# eprom_prog.net
KiCad netlist of a schematic drawn in EAGLE
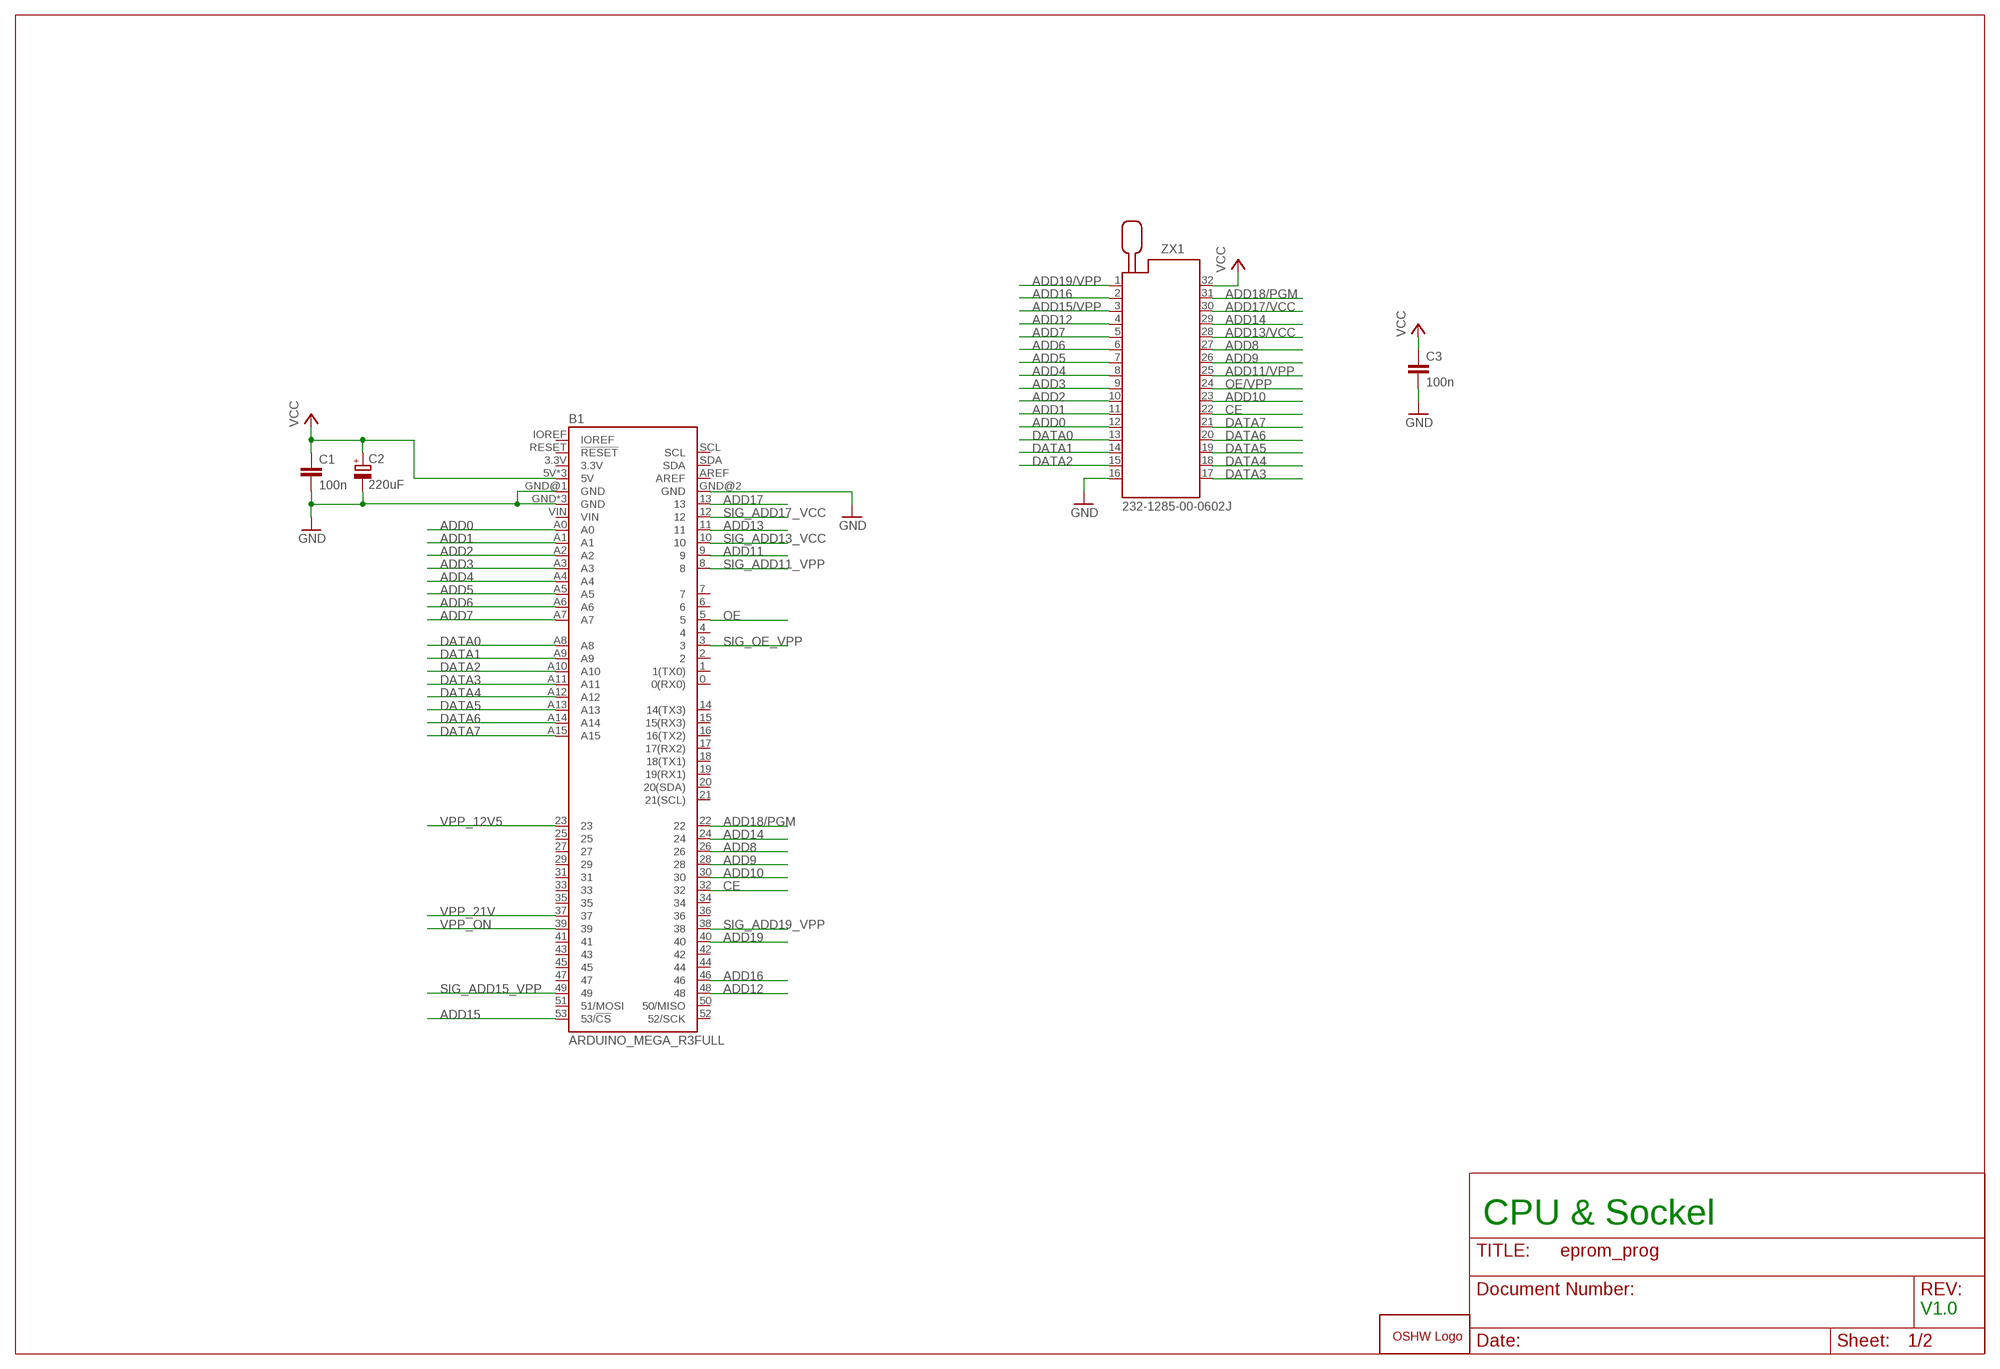
[diagram p0: schematic, sheet 1]
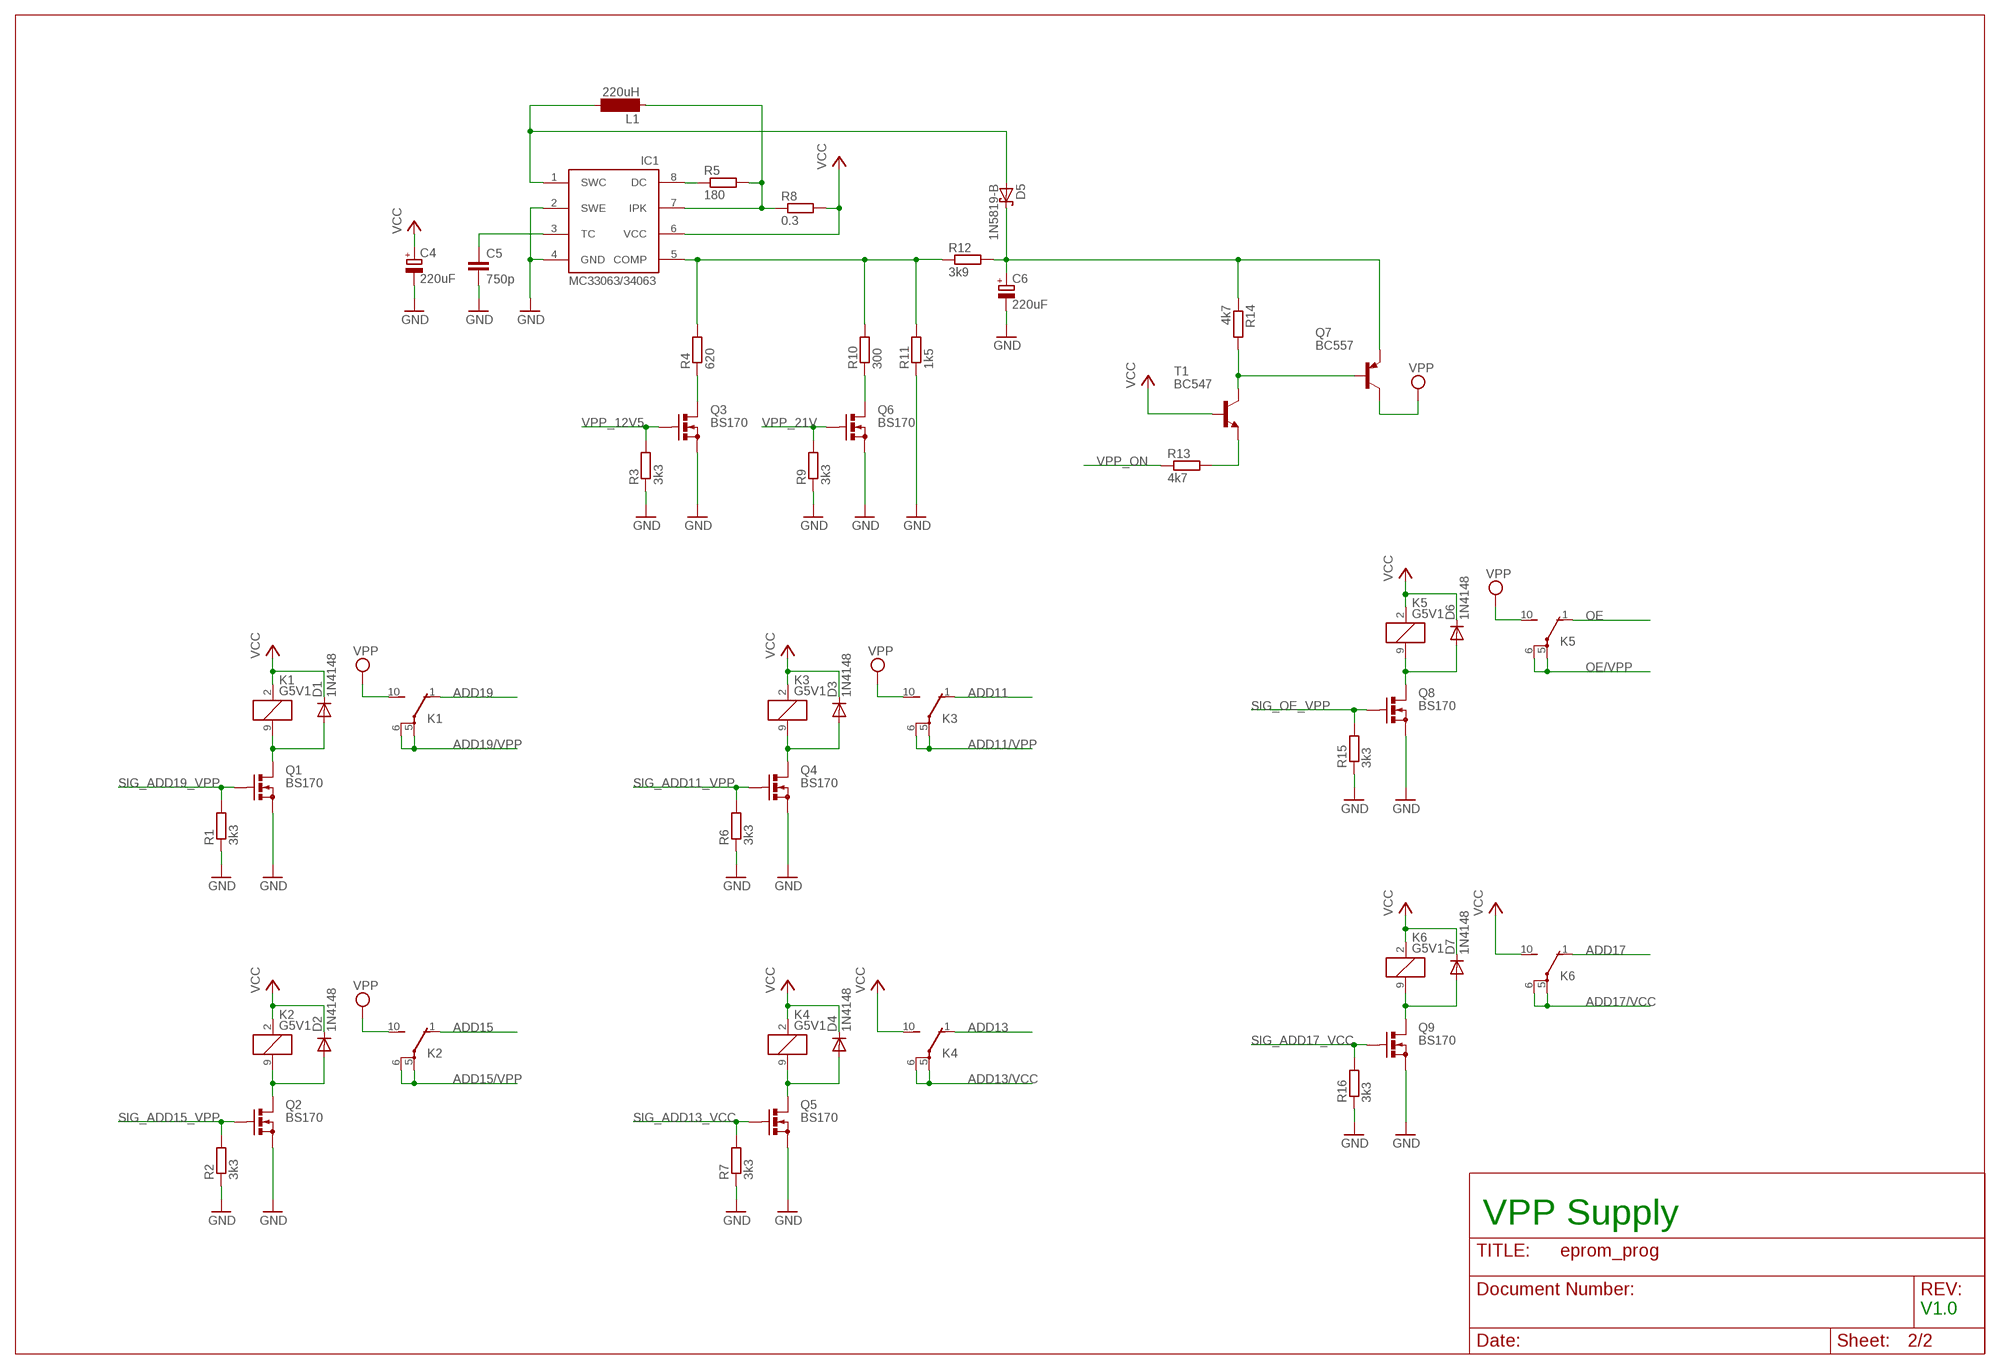
[diagram p1: schematic, sheet 2]

(export (version "E")
  (design (tool "Eeschema 10.0.6"))
  (components
    (comp (ref "B1")
      (value "ARDUINO_MEGA_R3FULL")
      (footprint "eagle-import:ARDUINO_MEGA_NO_SILK")
      (libsource (lib "eagle-import") (part "ARDUINO_MEGA_R3FULL"))
    )
    (comp (ref "C1")
      (value "100n")
      (footprint "eagle-import:C050-024X044")
      (libsource (lib "eagle-import") (part "C-EU050-024X044"))
    )
    (comp (ref "C2")
      (value "220uF")
      (footprint "eagle-import:E2,5-6")
      (libsource (lib "eagle-import") (part "CPOL-EUE2.5-6"))
    )
    (comp (ref "C3")
      (value "100n")
      (footprint "eagle-import:C050-024X044")
      (libsource (lib "eagle-import") (part "C-EU050-024X044"))
    )
    (comp (ref "GOLD_ORB_SM1")
      (value "OSHWLOGOLOGO8MM")
      (footprint "eagle-import:OSHW_8MM")
      (libsource (lib "eagle-import") (part "OSHWLOGOLOGO8MM"))
    )
    (comp (ref "ZX1")
      (value "232-1285-00-0602J")
      (footprint "eagle-import:232-1285-00-0602J")
      (fields (field (name "MF") "3M"))
      (libsource (lib "eagle-import") (part "232-?1285-00-0602J"))
    )
    (comp (ref "C4")
      (value "220uF")
      (footprint "eagle-import:E2,5-6")
      (libsource (lib "eagle-import") (part "CPOL-EUE2.5-6"))
    )
    (comp (ref "C5")
      (value "750p")
      (footprint "eagle-import:C050-024X044")
      (libsource (lib "eagle-import") (part "C-EU050-024X044"))
    )
    (comp (ref "C6")
      (value "220uF")
      (footprint "eagle-import:E2,5-6")
      (libsource (lib "eagle-import") (part "CPOL-EUE2.5-6"))
    )
    (comp (ref "D1")
      (value "1N4148")
      (footprint "eagle-import:DO35-7")
      (libsource (lib "eagle-import") (part "1N4148DO35-7"))
    )
    (comp (ref "D2")
      (value "1N4148")
      (footprint "eagle-import:DO35-7")
      (libsource (lib "eagle-import") (part "1N4148DO35-7"))
    )
    (comp (ref "D3")
      (value "1N4148")
      (footprint "eagle-import:DO35-7")
      (libsource (lib "eagle-import") (part "1N4148DO35-7"))
    )
    (comp (ref "D4")
      (value "1N4148")
      (footprint "eagle-import:DO35-7")
      (libsource (lib "eagle-import") (part "1N4148DO35-7"))
    )
    (comp (ref "D5")
      (value "1N5819-B")
      (footprint "eagle-import:DO41-7.6")
      (libsource (lib "eagle-import") (part "1N5819-B"))
    )
    (comp (ref "D6")
      (value "1N4148")
      (footprint "eagle-import:DO35-7")
      (libsource (lib "eagle-import") (part "1N4148DO35-7"))
    )
    (comp (ref "D7")
      (value "1N4148")
      (footprint "eagle-import:DO35-7")
      (libsource (lib "eagle-import") (part "1N4148DO35-7"))
    )
    (comp (ref "IC1")
      (value "MC33063/MC34063P")
      (footprint "eagle-import:DIL08")
      (libsource (lib "eagle-import") (part "MC33063/MC34063P"))
    )
    (comp (ref "K1")
      (value "G5V1")
      (footprint "eagle-import:G5V1")
      (fields (field (name "MPN") "G5V-1-DC24"))
      (libsource (lib "eagle-import") (part "G5V1"))
    )
    (comp (ref "K2")
      (value "G5V1")
      (footprint "eagle-import:G5V1")
      (fields (field (name "MPN") "G5V-1-DC24"))
      (libsource (lib "eagle-import") (part "G5V1"))
    )
    (comp (ref "K3")
      (value "G5V1")
      (footprint "eagle-import:G5V1")
      (fields (field (name "MPN") "G5V-1-DC24"))
      (libsource (lib "eagle-import") (part "G5V1"))
    )
    (comp (ref "K4")
      (value "G5V1")
      (footprint "eagle-import:G5V1")
      (fields (field (name "MPN") "G5V-1-DC24"))
      (libsource (lib "eagle-import") (part "G5V1"))
    )
    (comp (ref "K5")
      (value "G5V1")
      (footprint "eagle-import:G5V1")
      (fields (field (name "MPN") "G5V-1-DC24"))
      (libsource (lib "eagle-import") (part "G5V1"))
    )
    (comp (ref "K6")
      (value "G5V1")
      (footprint "eagle-import:G5V1")
      (fields (field (name "MPN") "G5V-1-DC24"))
      (libsource (lib "eagle-import") (part "G5V1"))
    )
    (comp (ref "L1")
      (value "220uH")
      (footprint "eagle-import:SD12_1000")
      (libsource (lib "eagle-import") (part "SD12-1000"))
    )
    (comp (ref "Q1")
      (value "BS170")
      (footprint "eagle-import:SOT54E")
      (libsource (lib "eagle-import") (part "BS170"))
    )
    (comp (ref "Q2")
      (value "BS170")
      (footprint "eagle-import:SOT54E")
      (libsource (lib "eagle-import") (part "BS170"))
    )
    (comp (ref "Q3")
      (value "BS170")
      (footprint "eagle-import:SOT54E")
      (libsource (lib "eagle-import") (part "BS170"))
    )
    (comp (ref "Q4")
      (value "BS170")
      (footprint "eagle-import:SOT54E")
      (libsource (lib "eagle-import") (part "BS170"))
    )
    (comp (ref "Q5")
      (value "BS170")
      (footprint "eagle-import:SOT54E")
      (libsource (lib "eagle-import") (part "BS170"))
    )
    (comp (ref "Q6")
      (value "BS170")
      (footprint "eagle-import:SOT54E")
      (libsource (lib "eagle-import") (part "BS170"))
    )
    (comp (ref "Q7")
      (value "BC557")
      (footprint "eagle-import:TO92")
      (libsource (lib "eagle-import") (part "BC557"))
    )
    (comp (ref "Q8")
      (value "BS170")
      (footprint "eagle-import:SOT54E")
      (libsource (lib "eagle-import") (part "BS170"))
    )
    (comp (ref "Q9")
      (value "BS170")
      (footprint "eagle-import:SOT54E")
      (libsource (lib "eagle-import") (part "BS170"))
    )
    (comp (ref "R1")
      (value "3k3")
      (footprint "eagle-import:0207_2V")
      (libsource (lib "eagle-import") (part "R-EU_0207/2V"))
    )
    (comp (ref "R2")
      (value "3k3")
      (footprint "eagle-import:0207_2V")
      (libsource (lib "eagle-import") (part "R-EU_0207/2V"))
    )
    (comp (ref "R3")
      (value "3k3")
      (footprint "eagle-import:0207_2V")
      (libsource (lib "eagle-import") (part "R-EU_0207/2V"))
    )
    (comp (ref "R4")
      (value "620")
      (footprint "eagle-import:0207_2V")
      (libsource (lib "eagle-import") (part "R-EU_0207/2V"))
    )
    (comp (ref "R5")
      (value "180")
      (footprint "eagle-import:0207_2V")
      (libsource (lib "eagle-import") (part "R-EU_0207/2V"))
    )
    (comp (ref "R6")
      (value "3k3")
      (footprint "eagle-import:0207_2V")
      (libsource (lib "eagle-import") (part "R-EU_0207/2V"))
    )
    (comp (ref "R7")
      (value "3k3")
      (footprint "eagle-import:0207_2V")
      (libsource (lib "eagle-import") (part "R-EU_0207/2V"))
    )
    (comp (ref "R8")
      (value "0.3")
      (footprint "eagle-import:0207_2V")
      (libsource (lib "eagle-import") (part "R-EU_0207/2V"))
    )
    (comp (ref "R9")
      (value "3k3")
      (footprint "eagle-import:0207_2V")
      (libsource (lib "eagle-import") (part "R-EU_0207/2V"))
    )
    (comp (ref "R10")
      (value "300")
      (footprint "eagle-import:0207_2V")
      (libsource (lib "eagle-import") (part "R-EU_0207/2V"))
    )
    (comp (ref "R11")
      (value "1k5")
      (footprint "eagle-import:0207_2V")
      (libsource (lib "eagle-import") (part "R-EU_0207/2V"))
    )
    (comp (ref "R12")
      (value "3k9")
      (footprint "eagle-import:0207_2V")
      (libsource (lib "eagle-import") (part "R-EU_0207/2V"))
    )
    (comp (ref "R13")
      (value "4k7")
      (footprint "eagle-import:0207_2V")
      (libsource (lib "eagle-import") (part "R-EU_0207/2V"))
    )
    (comp (ref "R14")
      (value "4k7")
      (footprint "eagle-import:0207_2V")
      (libsource (lib "eagle-import") (part "R-EU_0207/2V"))
    )
    (comp (ref "R15")
      (value "3k3")
      (footprint "eagle-import:0207_2V")
      (libsource (lib "eagle-import") (part "R-EU_0207/2V"))
    )
    (comp (ref "R16")
      (value "3k3")
      (footprint "eagle-import:0207_2V")
      (libsource (lib "eagle-import") (part "R-EU_0207/2V"))
    )
    (comp (ref "T1")
      (value "BC547")
      (footprint "eagle-import:TO92")
      (libsource (lib "eagle-import") (part "BC547"))
    )
  )
  (nets
    (net (code "1") (name "ADD0") (class "Default")
      (node (ref "B1") (pin "A0") (pinfunction "A0_A0") (pintype "bidirectional"))
      (node (ref "ZX1") (pin "12") (pinfunction "12_12") (pintype "passive"))
    )
    (net (code "2") (name "ADD1") (class "Default")
      (node (ref "B1") (pin "A1") (pinfunction "A1_A1") (pintype "bidirectional"))
      (node (ref "ZX1") (pin "11") (pinfunction "11_11") (pintype "passive"))
    )
    (net (code "3") (name "ADD2") (class "Default")
      (node (ref "B1") (pin "A2") (pinfunction "A2_A2") (pintype "bidirectional"))
      (node (ref "ZX1") (pin "10") (pinfunction "10_10") (pintype "passive"))
    )
    (net (code "4") (name "ADD3") (class "Default")
      (node (ref "B1") (pin "A3") (pinfunction "A3_A3") (pintype "bidirectional"))
      (node (ref "ZX1") (pin "9") (pinfunction "9_9") (pintype "passive"))
    )
    (net (code "5") (name "ADD4") (class "Default")
      (node (ref "B1") (pin "A4") (pinfunction "A4_A4") (pintype "bidirectional"))
      (node (ref "ZX1") (pin "8") (pinfunction "8_8") (pintype "passive"))
    )
    (net (code "6") (name "ADD5") (class "Default")
      (node (ref "B1") (pin "A5") (pinfunction "A5_A5") (pintype "bidirectional"))
      (node (ref "ZX1") (pin "7") (pinfunction "7_7") (pintype "passive"))
    )
    (net (code "7") (name "ADD6") (class "Default")
      (node (ref "B1") (pin "A6") (pinfunction "A6_A6") (pintype "bidirectional"))
      (node (ref "ZX1") (pin "6") (pinfunction "6_6") (pintype "passive"))
    )
    (net (code "8") (name "ADD7") (class "Default")
      (node (ref "B1") (pin "A7") (pinfunction "A7_A7") (pintype "bidirectional"))
      (node (ref "ZX1") (pin "5") (pinfunction "5_5") (pintype "passive"))
    )
    (net (code "9") (name "ADD8") (class "Default")
      (node (ref "B1") (pin "26") (pinfunction "26_26") (pintype "bidirectional"))
      (node (ref "ZX1") (pin "27") (pinfunction "27_27") (pintype "passive"))
    )
    (net (code "10") (name "ADD9") (class "Default")
      (node (ref "B1") (pin "28") (pinfunction "28_28") (pintype "bidirectional"))
      (node (ref "ZX1") (pin "26") (pinfunction "26_26") (pintype "passive"))
    )
    (net (code "11") (name "ADD10") (class "Default")
      (node (ref "B1") (pin "30") (pinfunction "30_30") (pintype "bidirectional"))
      (node (ref "ZX1") (pin "23") (pinfunction "23_23") (pintype "passive"))
    )
    (net (code "12") (name "ADD11") (class "Default")
      (node (ref "B1") (pin "9") (pinfunction "9_9") (pintype "bidirectional"))
      (node (ref "K3") (pin "1") (pinfunction "O_1") (pintype "passive"))
    )
    (net (code "13") (name "ADD11{slash}VPP") (class "Default")
      (node (ref "K3") (pin "5") (pinfunction "P_5") (pintype "passive"))
      (node (ref "K3") (pin "6") (pinfunction "P_6") (pintype "passive"))
      (node (ref "ZX1") (pin "25") (pinfunction "25_25") (pintype "passive"))
    )
    (net (code "14") (name "ADD12") (class "Default")
      (node (ref "B1") (pin "48") (pinfunction "48_48") (pintype "bidirectional"))
      (node (ref "ZX1") (pin "4") (pinfunction "4_4") (pintype "passive"))
    )
    (net (code "15") (name "ADD13") (class "Default")
      (node (ref "B1") (pin "11") (pinfunction "11_11") (pintype "bidirectional"))
      (node (ref "K4") (pin "1") (pinfunction "O_1") (pintype "passive"))
    )
    (net (code "16") (name "ADD13{slash}VCC") (class "Default")
      (node (ref "K4") (pin "5") (pinfunction "P_5") (pintype "passive"))
      (node (ref "K4") (pin "6") (pinfunction "P_6") (pintype "passive"))
      (node (ref "ZX1") (pin "28") (pinfunction "28_28") (pintype "passive"))
    )
    (net (code "17") (name "ADD14") (class "Default")
      (node (ref "B1") (pin "24") (pinfunction "24_24") (pintype "bidirectional"))
      (node (ref "ZX1") (pin "29") (pinfunction "29_29") (pintype "passive"))
    )
    (net (code "18") (name "ADD15") (class "Default")
      (node (ref "B1") (pin "53") (pinfunction "53/~{CS}_53") (pintype "bidirectional"))
      (node (ref "K2") (pin "1") (pinfunction "O_1") (pintype "passive"))
    )
    (net (code "19") (name "ADD15{slash}VPP") (class "Default")
      (node (ref "K2") (pin "5") (pinfunction "P_5") (pintype "passive"))
      (node (ref "K2") (pin "6") (pinfunction "P_6") (pintype "passive"))
      (node (ref "ZX1") (pin "3") (pinfunction "3_3") (pintype "passive"))
    )
    (net (code "20") (name "ADD16") (class "Default")
      (node (ref "B1") (pin "46") (pinfunction "46_46") (pintype "bidirectional"))
      (node (ref "ZX1") (pin "2") (pinfunction "2_2") (pintype "passive"))
    )
    (net (code "21") (name "ADD17") (class "Default")
      (node (ref "B1") (pin "13") (pinfunction "13_13") (pintype "bidirectional"))
      (node (ref "K6") (pin "1") (pinfunction "O_1") (pintype "passive"))
    )
    (net (code "22") (name "ADD17{slash}VCC") (class "Default")
      (node (ref "K6") (pin "5") (pinfunction "P_5") (pintype "passive"))
      (node (ref "K6") (pin "6") (pinfunction "P_6") (pintype "passive"))
      (node (ref "ZX1") (pin "30") (pinfunction "30_30") (pintype "passive"))
    )
    (net (code "23") (name "ADD18{slash}PGM") (class "Default")
      (node (ref "B1") (pin "22") (pinfunction "22_22") (pintype "bidirectional"))
      (node (ref "ZX1") (pin "31") (pinfunction "31_31") (pintype "passive"))
    )
    (net (code "24") (name "ADD19") (class "Default")
      (node (ref "B1") (pin "40") (pinfunction "40_40") (pintype "bidirectional"))
      (node (ref "K1") (pin "1") (pinfunction "O_1") (pintype "passive"))
    )
    (net (code "25") (name "ADD19{slash}VPP") (class "Default")
      (node (ref "K1") (pin "5") (pinfunction "P_5") (pintype "passive"))
      (node (ref "K1") (pin "6") (pinfunction "P_6") (pintype "passive"))
      (node (ref "ZX1") (pin "1") (pinfunction "1_1") (pintype "passive"))
    )
    (net (code "26") (name "CE") (class "Default")
      (node (ref "B1") (pin "32") (pinfunction "32_32") (pintype "bidirectional"))
      (node (ref "ZX1") (pin "22") (pinfunction "22_22") (pintype "passive"))
    )
    (net (code "27") (name "DATA0") (class "Default")
      (node (ref "B1") (pin "A8") (pinfunction "A8_A8") (pintype "bidirectional"))
      (node (ref "ZX1") (pin "13") (pinfunction "13_13") (pintype "passive"))
    )
    (net (code "28") (name "DATA1") (class "Default")
      (node (ref "B1") (pin "A9") (pinfunction "A9_A9") (pintype "bidirectional"))
      (node (ref "ZX1") (pin "14") (pinfunction "14_14") (pintype "passive"))
    )
    (net (code "29") (name "DATA2") (class "Default")
      (node (ref "B1") (pin "A10") (pinfunction "A10_A10") (pintype "bidirectional"))
      (node (ref "ZX1") (pin "15") (pinfunction "15_15") (pintype "passive"))
    )
    (net (code "30") (name "DATA3") (class "Default")
      (node (ref "B1") (pin "A11") (pinfunction "A11_A11") (pintype "bidirectional"))
      (node (ref "ZX1") (pin "17") (pinfunction "17_17") (pintype "passive"))
    )
    (net (code "31") (name "DATA4") (class "Default")
      (node (ref "B1") (pin "A12") (pinfunction "A12_A12") (pintype "bidirectional"))
      (node (ref "ZX1") (pin "18") (pinfunction "18_18") (pintype "passive"))
    )
    (net (code "32") (name "DATA5") (class "Default")
      (node (ref "B1") (pin "A13") (pinfunction "A13_A13") (pintype "bidirectional"))
      (node (ref "ZX1") (pin "19") (pinfunction "19_19") (pintype "passive"))
    )
    (net (code "33") (name "DATA6") (class "Default")
      (node (ref "B1") (pin "A14") (pinfunction "A14_A14") (pintype "bidirectional"))
      (node (ref "ZX1") (pin "20") (pinfunction "20_20") (pintype "passive"))
    )
    (net (code "34") (name "DATA7") (class "Default")
      (node (ref "B1") (pin "A15") (pinfunction "A15_A15") (pintype "bidirectional"))
      (node (ref "ZX1") (pin "21") (pinfunction "21_21") (pintype "passive"))
    )
    (net (code "35") (name "GND") (class "Default")
      (node (ref "B1") (pin "GND") (pinfunction "GND_GND") (pintype "bidirectional"))
      (node (ref "B1") (pin "GND@1") (pinfunction "GND_GND@1") (pintype "bidirectional"))
      (node (ref "B1") (pin "GND@2") (pinfunction "GND_GND@2") (pintype "bidirectional"))
      (node (ref "B1") (pin "GND@3") (pinfunction "GND_GND@3") (pintype "bidirectional"))
      (node (ref "B1") (pin "GND@4") (pinfunction "GND_GND@4") (pintype "bidirectional"))
      (node (ref "C1") (pin "2") (pinfunction "2_2") (pintype "passive"))
      (node (ref "C2") (pin "-") (pinfunction "-_-") (pintype "passive"))
      (node (ref "C3") (pin "2") (pinfunction "2_2") (pintype "passive"))
      (node (ref "C4") (pin "-") (pinfunction "-_-") (pintype "passive"))
      (node (ref "C5") (pin "2") (pinfunction "2_2") (pintype "passive"))
      (node (ref "C6") (pin "-") (pinfunction "-_-") (pintype "passive"))
      (node (ref "IC1") (pin "2") (pinfunction "SWE_2") (pintype "input"))
      (node (ref "IC1") (pin "4") (pinfunction "GND_4") (pintype "power_in"))
      (node (ref "Q1") (pin "S") (pinfunction "S_S") (pintype "passive"))
      (node (ref "Q2") (pin "S") (pinfunction "S_S") (pintype "passive"))
      (node (ref "Q3") (pin "S") (pinfunction "S_S") (pintype "passive"))
      (node (ref "Q4") (pin "S") (pinfunction "S_S") (pintype "passive"))
      (node (ref "Q5") (pin "S") (pinfunction "S_S") (pintype "passive"))
      (node (ref "Q6") (pin "S") (pinfunction "S_S") (pintype "passive"))
      (node (ref "Q8") (pin "S") (pinfunction "S_S") (pintype "passive"))
      (node (ref "Q9") (pin "S") (pinfunction "S_S") (pintype "passive"))
      (node (ref "R1") (pin "1") (pinfunction "1_1") (pintype "passive"))
      (node (ref "R11") (pin "1") (pinfunction "1_1") (pintype "passive"))
      (node (ref "R15") (pin "1") (pinfunction "1_1") (pintype "passive"))
      (node (ref "R16") (pin "1") (pinfunction "1_1") (pintype "passive"))
      (node (ref "R2") (pin "1") (pinfunction "1_1") (pintype "passive"))
      (node (ref "R3") (pin "1") (pinfunction "1_1") (pintype "passive"))
      (node (ref "R6") (pin "1") (pinfunction "1_1") (pintype "passive"))
      (node (ref "R7") (pin "1") (pinfunction "1_1") (pintype "passive"))
      (node (ref "R9") (pin "1") (pinfunction "1_1") (pintype "passive"))
      (node (ref "ZX1") (pin "16") (pinfunction "16_16") (pintype "passive"))
    )
    (net (code "36") (name "Net-(IC1-COMP)") (class "Default")
      (node (ref "IC1") (pin "5") (pinfunction "COMP_5") (pintype "input"))
      (node (ref "R10") (pin "2") (pinfunction "2_2") (pintype "passive"))
      (node (ref "R11") (pin "2") (pinfunction "2_2") (pintype "passive"))
      (node (ref "R12") (pin "1") (pinfunction "1_1") (pintype "passive"))
      (node (ref "R4") (pin "2") (pinfunction "2_2") (pintype "passive"))
    )
    (net (code "37") (name "Net-(IC1-DC)") (class "Default")
      (node (ref "IC1") (pin "8") (pinfunction "DC_8") (pintype "input"))
      (node (ref "R5") (pin "1") (pinfunction "1_1") (pintype "passive"))
    )
    (net (code "38") (name "Net-(IC1-IPK)") (class "Default")
      (node (ref "IC1") (pin "7") (pinfunction "IPK_7") (pintype "bidirectional"))
      (node (ref "L1") (pin "1") (pinfunction "1_1") (pintype "passive"))
      (node (ref "R5") (pin "2") (pinfunction "2_2") (pintype "passive"))
      (node (ref "R8") (pin "1") (pinfunction "1_1") (pintype "passive"))
    )
    (net (code "39") (name "Net-(IC1-SWC)") (class "Default")
      (node (ref "D5") (pin "A") (pinfunction "A_A") (pintype "passive"))
      (node (ref "IC1") (pin "1") (pinfunction "SWC_1") (pintype "input"))
      (node (ref "L1") (pin "2") (pinfunction "2_2") (pintype "passive"))
    )
    (net (code "40") (name "Net-(IC1-TC)") (class "Default")
      (node (ref "C5") (pin "1") (pinfunction "1_1") (pintype "passive"))
      (node (ref "IC1") (pin "3") (pinfunction "TC_3") (pintype "input"))
    )
    (net (code "41") (name "Net-(K1A-2)") (class "Default")
      (node (ref "D1") (pin "A") (pinfunction "A_A") (pintype "passive"))
      (node (ref "K1") (pin "9") (pinfunction "2_9") (pintype "passive"))
      (node (ref "Q1") (pin "D") (pinfunction "D_D") (pintype "passive"))
    )
    (net (code "42") (name "Net-(K2A-2)") (class "Default")
      (node (ref "D2") (pin "A") (pinfunction "A_A") (pintype "passive"))
      (node (ref "K2") (pin "9") (pinfunction "2_9") (pintype "passive"))
      (node (ref "Q2") (pin "D") (pinfunction "D_D") (pintype "passive"))
    )
    (net (code "43") (name "Net-(K3A-2)") (class "Default")
      (node (ref "D3") (pin "A") (pinfunction "A_A") (pintype "passive"))
      (node (ref "K3") (pin "9") (pinfunction "2_9") (pintype "passive"))
      (node (ref "Q4") (pin "D") (pinfunction "D_D") (pintype "passive"))
    )
    (net (code "44") (name "Net-(K4A-2)") (class "Default")
      (node (ref "D4") (pin "A") (pinfunction "A_A") (pintype "passive"))
      (node (ref "K4") (pin "9") (pinfunction "2_9") (pintype "passive"))
      (node (ref "Q5") (pin "D") (pinfunction "D_D") (pintype "passive"))
    )
    (net (code "45") (name "Net-(K5A-2)") (class "Default")
      (node (ref "D6") (pin "A") (pinfunction "A_A") (pintype "passive"))
      (node (ref "K5") (pin "9") (pinfunction "2_9") (pintype "passive"))
      (node (ref "Q8") (pin "D") (pinfunction "D_D") (pintype "passive"))
    )
    (net (code "46") (name "Net-(K6A-2)") (class "Default")
      (node (ref "D7") (pin "A") (pinfunction "A_A") (pintype "passive"))
      (node (ref "K6") (pin "9") (pinfunction "2_9") (pintype "passive"))
      (node (ref "Q9") (pin "D") (pinfunction "D_D") (pintype "passive"))
    )
    (net (code "47") (name "Net-(Q3-PadD)") (class "Default")
      (node (ref "Q3") (pin "D") (pinfunction "D_D") (pintype "passive"))
      (node (ref "R4") (pin "1") (pinfunction "1_1") (pintype "passive"))
    )
    (net (code "48") (name "Net-(Q6-PadD)") (class "Default")
      (node (ref "Q6") (pin "D") (pinfunction "D_D") (pintype "passive"))
      (node (ref "R10") (pin "1") (pinfunction "1_1") (pintype "passive"))
    )
    (net (code "49") (name "Net-(Q7-B)") (class "Default")
      (node (ref "Q7") (pin "2") (pinfunction "B_2") (pintype "passive"))
      (node (ref "R14") (pin "2") (pinfunction "2_2") (pintype "passive"))
      (node (ref "T1") (pin "3") (pinfunction "C_3") (pintype "passive"))
    )
    (net (code "50") (name "Net-(Q7-E)") (class "Default")
      (node (ref "C6") (pin "+") (pinfunction "+_+") (pintype "passive"))
      (node (ref "D5") (pin "C") (pinfunction "C_C") (pintype "passive"))
      (node (ref "Q7") (pin "1") (pinfunction "E_1") (pintype "passive"))
      (node (ref "R12") (pin "2") (pinfunction "2_2") (pintype "passive"))
      (node (ref "R14") (pin "1") (pinfunction "1_1") (pintype "passive"))
    )
    (net (code "51") (name "Net-(T1-E)") (class "Default")
      (node (ref "R13") (pin "2") (pinfunction "2_2") (pintype "passive"))
      (node (ref "T1") (pin "1") (pinfunction "E_1") (pintype "passive"))
    )
    (net (code "52") (name "OE") (class "Default")
      (node (ref "B1") (pin "5") (pinfunction "5_5") (pintype "bidirectional"))
      (node (ref "K5") (pin "1") (pinfunction "O_1") (pintype "passive"))
    )
    (net (code "53") (name "OE{slash}VPP") (class "Default")
      (node (ref "K5") (pin "5") (pinfunction "P_5") (pintype "passive"))
      (node (ref "K5") (pin "6") (pinfunction "P_6") (pintype "passive"))
      (node (ref "ZX1") (pin "24") (pinfunction "24_24") (pintype "passive"))
    )
    (net (code "54") (name "SIG_ADD11_VPP") (class "Default")
      (node (ref "B1") (pin "8") (pinfunction "8_8") (pintype "bidirectional"))
      (node (ref "Q4") (pin "G") (pinfunction "G_G") (pintype "passive"))
      (node (ref "R6") (pin "2") (pinfunction "2_2") (pintype "passive"))
    )
    (net (code "55") (name "SIG_ADD13_VCC") (class "Default")
      (node (ref "B1") (pin "10") (pinfunction "10_10") (pintype "bidirectional"))
      (node (ref "Q5") (pin "G") (pinfunction "G_G") (pintype "passive"))
      (node (ref "R7") (pin "2") (pinfunction "2_2") (pintype "passive"))
    )
    (net (code "56") (name "SIG_ADD15_VPP") (class "Default")
      (node (ref "B1") (pin "49") (pinfunction "49_49") (pintype "bidirectional"))
      (node (ref "Q2") (pin "G") (pinfunction "G_G") (pintype "passive"))
      (node (ref "R2") (pin "2") (pinfunction "2_2") (pintype "passive"))
    )
    (net (code "57") (name "SIG_ADD17_VCC") (class "Default")
      (node (ref "B1") (pin "12") (pinfunction "12_12") (pintype "bidirectional"))
      (node (ref "Q9") (pin "G") (pinfunction "G_G") (pintype "passive"))
      (node (ref "R16") (pin "2") (pinfunction "2_2") (pintype "passive"))
    )
    (net (code "58") (name "SIG_ADD19_VPP") (class "Default")
      (node (ref "B1") (pin "38") (pinfunction "38_38") (pintype "bidirectional"))
      (node (ref "Q1") (pin "G") (pinfunction "G_G") (pintype "passive"))
      (node (ref "R1") (pin "2") (pinfunction "2_2") (pintype "passive"))
    )
    (net (code "59") (name "SIG_OE_VPP") (class "Default")
      (node (ref "B1") (pin "3") (pinfunction "3_3") (pintype "bidirectional"))
      (node (ref "Q8") (pin "G") (pinfunction "G_G") (pintype "passive"))
      (node (ref "R15") (pin "2") (pinfunction "2_2") (pintype "passive"))
    )
    (net (code "60") (name "VCC") (class "Default")
      (node (ref "B1") (pin "5V") (pinfunction "5V_5V") (pintype "bidirectional"))
      (node (ref "B1") (pin "5V@1") (pinfunction "5V_5V@1") (pintype "bidirectional"))
      (node (ref "B1") (pin "5V@2") (pinfunction "5V_5V@2") (pintype "bidirectional"))
      (node (ref "C1") (pin "1") (pinfunction "1_1") (pintype "passive"))
      (node (ref "C2") (pin "+") (pinfunction "+_+") (pintype "passive"))
      (node (ref "C3") (pin "1") (pinfunction "1_1") (pintype "passive"))
      (node (ref "C4") (pin "+") (pinfunction "+_+") (pintype "passive"))
      (node (ref "D1") (pin "C") (pinfunction "C_C") (pintype "passive"))
      (node (ref "D2") (pin "C") (pinfunction "C_C") (pintype "passive"))
      (node (ref "D3") (pin "C") (pinfunction "C_C") (pintype "passive"))
      (node (ref "D4") (pin "C") (pinfunction "C_C") (pintype "passive"))
      (node (ref "D6") (pin "C") (pinfunction "C_C") (pintype "passive"))
      (node (ref "D7") (pin "C") (pinfunction "C_C") (pintype "passive"))
      (node (ref "IC1") (pin "6") (pinfunction "VCC_6") (pintype "power_in"))
      (node (ref "K1") (pin "2") (pinfunction "1_2") (pintype "passive"))
      (node (ref "K2") (pin "2") (pinfunction "1_2") (pintype "passive"))
      (node (ref "K3") (pin "2") (pinfunction "1_2") (pintype "passive"))
      (node (ref "K4") (pin "10") (pinfunction "S_10") (pintype "passive"))
      (node (ref "K4") (pin "2") (pinfunction "1_2") (pintype "passive"))
      (node (ref "K5") (pin "2") (pinfunction "1_2") (pintype "passive"))
      (node (ref "K6") (pin "10") (pinfunction "S_10") (pintype "passive"))
      (node (ref "K6") (pin "2") (pinfunction "1_2") (pintype "passive"))
      (node (ref "R8") (pin "2") (pinfunction "2_2") (pintype "passive"))
      (node (ref "T1") (pin "2") (pinfunction "B_2") (pintype "passive"))
      (node (ref "ZX1") (pin "32") (pinfunction "32_32") (pintype "passive"))
    )
    (net (code "61") (name "VPP") (class "Default")
      (node (ref "K1") (pin "10") (pinfunction "S_10") (pintype "passive"))
      (node (ref "K2") (pin "10") (pinfunction "S_10") (pintype "passive"))
      (node (ref "K3") (pin "10") (pinfunction "S_10") (pintype "passive"))
      (node (ref "K5") (pin "10") (pinfunction "S_10") (pintype "passive"))
      (node (ref "Q7") (pin "3") (pinfunction "C_3") (pintype "passive"))
    )
    (net (code "62") (name "VPP_12V5") (class "Default")
      (node (ref "B1") (pin "23") (pinfunction "23_23") (pintype "bidirectional"))
      (node (ref "Q3") (pin "G") (pinfunction "G_G") (pintype "passive"))
      (node (ref "R3") (pin "2") (pinfunction "2_2") (pintype "passive"))
    )
    (net (code "63") (name "VPP_21V") (class "Default")
      (node (ref "B1") (pin "37") (pinfunction "37_37") (pintype "bidirectional"))
      (node (ref "Q6") (pin "G") (pinfunction "G_G") (pintype "passive"))
      (node (ref "R9") (pin "2") (pinfunction "2_2") (pintype "passive"))
    )
    (net (code "64") (name "VPP_ON") (class "Default")
      (node (ref "B1") (pin "39") (pinfunction "39_39") (pintype "bidirectional"))
      (node (ref "R13") (pin "1") (pinfunction "1_1") (pintype "passive"))
    )
    (net (code "65") (name "unconnected-(B1-0(RX0)-Pad0)") (class "Default")
      (node (ref "B1") (pin "0") (pinfunction "0(RX0)_0") (pintype "bidirectional"))
    )
    (net (code "66") (name "unconnected-(B1-1(TX0)-Pad1)") (class "Default")
      (node (ref "B1") (pin "1") (pinfunction "1(TX0)_1") (pintype "bidirectional"))
    )
    (net (code "67") (name "unconnected-(B1-14(TX3)-Pad14)") (class "Default")
      (node (ref "B1") (pin "14") (pinfunction "14(TX3)_14") (pintype "bidirectional"))
    )
    (net (code "68") (name "unconnected-(B1-15(RX3)-Pad15)") (class "Default")
      (node (ref "B1") (pin "15") (pinfunction "15(RX3)_15") (pintype "bidirectional"))
    )
    (net (code "69") (name "unconnected-(B1-16(TX2)-Pad16)") (class "Default")
      (node (ref "B1") (pin "16") (pinfunction "16(TX2)_16") (pintype "bidirectional"))
    )
    (net (code "70") (name "unconnected-(B1-17(RX2)-Pad17)") (class "Default")
      (node (ref "B1") (pin "17") (pinfunction "17(RX2)_17") (pintype "bidirectional"))
    )
    (net (code "71") (name "unconnected-(B1-18(TX1)-Pad18)") (class "Default")
      (node (ref "B1") (pin "18") (pinfunction "18(TX1)_18") (pintype "bidirectional"))
    )
    (net (code "72") (name "unconnected-(B1-19(RX1)-Pad19)") (class "Default")
      (node (ref "B1") (pin "19") (pinfunction "19(RX1)_19") (pintype "bidirectional"))
    )
    (net (code "73") (name "unconnected-(B1-20(SDA)-Pad20)") (class "Default")
      (node (ref "B1") (pin "20") (pinfunction "20(SDA)_20") (pintype "bidirectional"))
    )
    (net (code "74") (name "unconnected-(B1-21(SCL)-Pad21)") (class "Default")
      (node (ref "B1") (pin "21") (pinfunction "21(SCL)_21") (pintype "bidirectional"))
    )
    (net (code "75") (name "unconnected-(B1-50{slash}MISO-Pad50)") (class "Default")
      (node (ref "B1") (pin "50") (pinfunction "50/MISO_50") (pintype "bidirectional"))
    )
    (net (code "76") (name "unconnected-(B1-51{slash}MOSI-Pad51)") (class "Default")
      (node (ref "B1") (pin "51") (pinfunction "51/MOSI_51") (pintype "bidirectional"))
    )
    (net (code "77") (name "unconnected-(B1-52{slash}SCK-Pad52)") (class "Default")
      (node (ref "B1") (pin "52") (pinfunction "52/SCK_52") (pintype "bidirectional"))
    )
    (net (code "78") (name "unconnected-(B1-Pad2)") (class "Default")
      (node (ref "B1") (pin "2") (pinfunction "2_2") (pintype "bidirectional"))
    )
    (net (code "79") (name "unconnected-(B1-Pad3.3V)") (class "Default")
      (node (ref "B1") (pin "3.3V") (pinfunction "3.3V_3.3V") (pintype "bidirectional"))
    )
    (net (code "80") (name "unconnected-(B1-Pad4)") (class "Default")
      (node (ref "B1") (pin "4") (pinfunction "4_4") (pintype "bidirectional"))
    )
    (net (code "81") (name "unconnected-(B1-Pad6)") (class "Default")
      (node (ref "B1") (pin "6") (pinfunction "6_6") (pintype "bidirectional"))
    )
    (net (code "82") (name "unconnected-(B1-Pad7)") (class "Default")
      (node (ref "B1") (pin "7") (pinfunction "7_7") (pintype "bidirectional"))
    )
    (net (code "83") (name "unconnected-(B1-Pad25)") (class "Default")
      (node (ref "B1") (pin "25") (pinfunction "25_25") (pintype "bidirectional"))
    )
    (net (code "84") (name "unconnected-(B1-Pad27)") (class "Default")
      (node (ref "B1") (pin "27") (pinfunction "27_27") (pintype "bidirectional"))
    )
    (net (code "85") (name "unconnected-(B1-Pad29)") (class "Default")
      (node (ref "B1") (pin "29") (pinfunction "29_29") (pintype "bidirectional"))
    )
    (net (code "86") (name "unconnected-(B1-Pad31)") (class "Default")
      (node (ref "B1") (pin "31") (pinfunction "31_31") (pintype "bidirectional"))
    )
    (net (code "87") (name "unconnected-(B1-Pad33)") (class "Default")
      (node (ref "B1") (pin "33") (pinfunction "33_33") (pintype "bidirectional"))
    )
    (net (code "88") (name "unconnected-(B1-Pad34)") (class "Default")
      (node (ref "B1") (pin "34") (pinfunction "34_34") (pintype "bidirectional"))
    )
    (net (code "89") (name "unconnected-(B1-Pad35)") (class "Default")
      (node (ref "B1") (pin "35") (pinfunction "35_35") (pintype "bidirectional"))
    )
    (net (code "90") (name "unconnected-(B1-Pad36)") (class "Default")
      (node (ref "B1") (pin "36") (pinfunction "36_36") (pintype "bidirectional"))
    )
    (net (code "91") (name "unconnected-(B1-Pad41)") (class "Default")
      (node (ref "B1") (pin "41") (pinfunction "41_41") (pintype "bidirectional"))
    )
    (net (code "92") (name "unconnected-(B1-Pad42)") (class "Default")
      (node (ref "B1") (pin "42") (pinfunction "42_42") (pintype "bidirectional"))
    )
    (net (code "93") (name "unconnected-(B1-Pad43)") (class "Default")
      (node (ref "B1") (pin "43") (pinfunction "43_43") (pintype "bidirectional"))
    )
    (net (code "94") (name "unconnected-(B1-Pad44)") (class "Default")
      (node (ref "B1") (pin "44") (pinfunction "44_44") (pintype "bidirectional"))
    )
    (net (code "95") (name "unconnected-(B1-Pad45)") (class "Default")
      (node (ref "B1") (pin "45") (pinfunction "45_45") (pintype "bidirectional"))
    )
    (net (code "96") (name "unconnected-(B1-Pad47)") (class "Default")
      (node (ref "B1") (pin "47") (pinfunction "47_47") (pintype "bidirectional"))
    )
    (net (code "97") (name "unconnected-(B1-PadAREF)") (class "Default")
      (node (ref "B1") (pin "AREF") (pinfunction "AREF_AREF") (pintype "bidirectional"))
    )
    (net (code "98") (name "unconnected-(B1-PadIOREF)") (class "Default")
      (node (ref "B1") (pin "IOREF") (pinfunction "IOREF_IOREF") (pintype "bidirectional"))
    )
    (net (code "99") (name "unconnected-(B1-PadSCL)") (class "Default")
      (node (ref "B1") (pin "SCL") (pinfunction "SCL_SCL") (pintype "bidirectional"))
    )
    (net (code "100") (name "unconnected-(B1-PadSDA)") (class "Default")
      (node (ref "B1") (pin "SDA") (pinfunction "SDA_SDA") (pintype "bidirectional"))
    )
    (net (code "101") (name "unconnected-(B1-PadVIN)") (class "Default")
      (node (ref "B1") (pin "VIN") (pinfunction "VIN_VIN") (pintype "bidirectional"))
    )
    (net (code "102") (name "unconnected-(B1-~{RESET}-PadRESET)") (class "Default")
      (node (ref "B1") (pin "RESET") (pinfunction "~{RESET}_RESET") (pintype "bidirectional"))
    )
  )
)
